# light2pwm.net
KiCad netlist of a schematic drawn in EAGLE
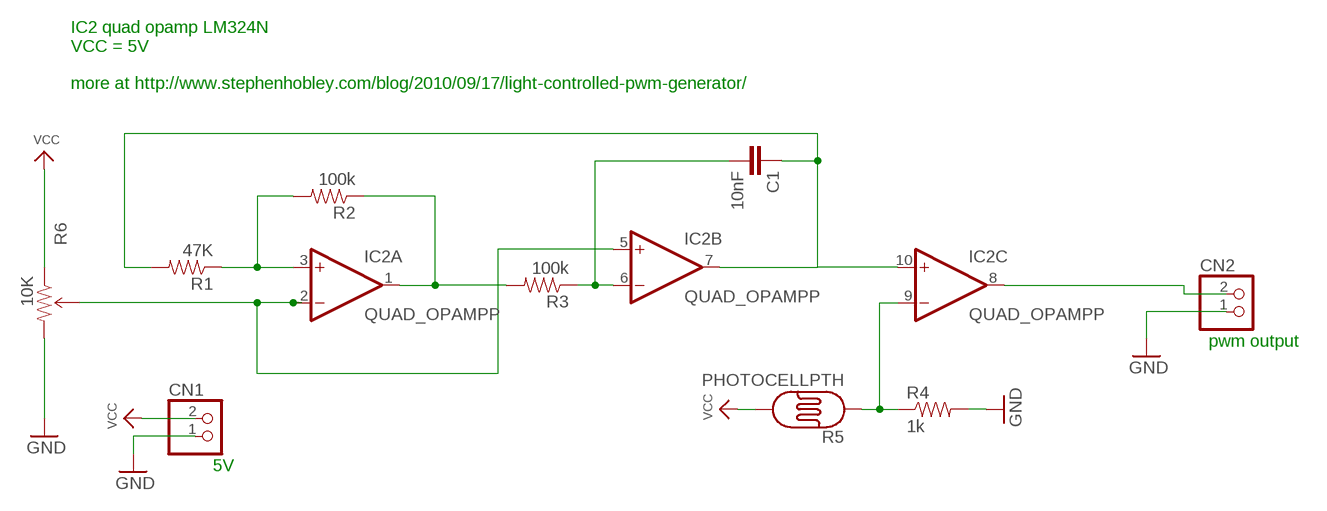
[diagram p0: schematic, sheet 1]

(export (version "E")
  (design (tool "Eeschema 10.0.6"))
  (components
    (comp (ref "C1")
      (value "10nF")
      (footprint "eagle-import:0402-CAP")
      (libsource (lib "eagle-import") (part "10NF-CER"))
    )
    (comp (ref "CN1")
      (value "JST_2PIN-THM")
      (footprint "eagle-import:JST-PH-2-THM")
      (libsource (lib "eagle-import") (part "JST_2PIN-THM"))
    )
    (comp (ref "CN2")
      (value "JST_2PIN-THM")
      (footprint "eagle-import:JST-PH-2-THM")
      (libsource (lib "eagle-import") (part "JST_2PIN-THM"))
    )
    (comp (ref "IC2")
      (value "QUAD_OPAMPP")
      (footprint "eagle-import:DIL14")
      (libsource (lib "eagle-import") (part "QUAD_OPAMPP"))
    )
    (comp (ref "R1")
      (value "47K")
      (footprint "eagle-import:AXIAL-0.3EZ")
      (libsource (lib "eagle-import") (part "RESISTOREZ"))
    )
    (comp (ref "R2")
      (value "100k")
      (footprint "eagle-import:AXIAL-0.3EZ")
      (libsource (lib "eagle-import") (part "RESISTOREZ"))
    )
    (comp (ref "R3")
      (value "100k")
      (footprint "eagle-import:AXIAL-0.3EZ")
      (libsource (lib "eagle-import") (part "RESISTOREZ"))
    )
    (comp (ref "R4")
      (value "1k")
      (footprint "eagle-import:AXIAL-0.3EZ")
      (libsource (lib "eagle-import") (part "RESISTOREZ"))
    )
    (comp (ref "R5")
      (value "PHOTOCELLPTH")
      (footprint "eagle-import:PHOTOCELL")
      (libsource (lib "eagle-import") (part "PHOTOCELLPTH"))
    )
    (comp (ref "R6")
      (value "10K")
      (footprint "eagle-import:3386U")
      (libsource (lib "eagle-import") (part "TRIMPOT-PTH-KNOB"))
    )
  )
  (nets
    (net (code "1") (name "GND") (class "Default")
      (node (ref "CN1") (pin "1") (pinfunction "2_1") (pintype "passive"))
      (node (ref "CN2") (pin "1") (pinfunction "2_1") (pintype "passive"))
      (node (ref "R4") (pin "P$2") (pinfunction "2_P$2") (pintype "passive"))
      (node (ref "R6") (pin "3") (pinfunction "CW_3") (pintype "passive"))
    )
    (net (code "2") (name "Net-(CN2-1)") (class "Default")
      (node (ref "CN2") (pin "2") (pinfunction "1_2") (pintype "passive"))
      (node (ref "IC2") (pin "8") (pinfunction "OUT_8") (pintype "output"))
    )
    (net (code "3") (name "Net-(IC2A-+IN)") (class "Default")
      (node (ref "IC2") (pin "3") (pinfunction "+IN_3") (pintype "input"))
      (node (ref "R1") (pin "P$1") (pinfunction "1_P$1") (pintype "passive"))
      (node (ref "R2") (pin "P$2") (pinfunction "2_P$2") (pintype "passive"))
    )
    (net (code "4") (name "Net-(IC2A--IN)") (class "Default")
      (node (ref "IC2") (pin "2") (pinfunction "-IN_2") (pintype "input"))
      (node (ref "IC2") (pin "5") (pinfunction "+IN_5") (pintype "input"))
      (node (ref "R6") (pin "2") (pinfunction "WIPER_2") (pintype "passive"))
    )
    (net (code "5") (name "Net-(IC2A-OUT)") (class "Default")
      (node (ref "IC2") (pin "1") (pinfunction "OUT_1") (pintype "output"))
      (node (ref "R2") (pin "P$1") (pinfunction "1_P$1") (pintype "passive"))
      (node (ref "R3") (pin "P$2") (pinfunction "2_P$2") (pintype "passive"))
    )
    (net (code "6") (name "Net-(IC2B--IN)") (class "Default")
      (node (ref "C1") (pin "2") (pinfunction "2_2") (pintype "passive"))
      (node (ref "IC2") (pin "6") (pinfunction "-IN_6") (pintype "input"))
      (node (ref "R3") (pin "P$1") (pinfunction "1_P$1") (pintype "passive"))
    )
    (net (code "7") (name "Net-(IC2B-OUT)") (class "Default")
      (node (ref "C1") (pin "1") (pinfunction "1_1") (pintype "passive"))
      (node (ref "IC2") (pin "10") (pinfunction "+IN_10") (pintype "input"))
      (node (ref "IC2") (pin "7") (pinfunction "OUT_7") (pintype "output"))
      (node (ref "R1") (pin "P$2") (pinfunction "2_P$2") (pintype "passive"))
    )
    (net (code "8") (name "Net-(IC2C--IN)") (class "Default")
      (node (ref "IC2") (pin "9") (pinfunction "-IN_9") (pintype "input"))
      (node (ref "R4") (pin "P$1") (pinfunction "1_P$1") (pintype "passive"))
      (node (ref "R5") (pin "1") (pinfunction "P$1_1") (pintype "bidirectional"))
    )
    (net (code "9") (name "VCC") (class "Default")
      (node (ref "CN1") (pin "2") (pinfunction "1_2") (pintype "passive"))
      (node (ref "R5") (pin "2") (pinfunction "P$2_2") (pintype "bidirectional"))
      (node (ref "R6") (pin "1") (pinfunction "CCW_1") (pintype "passive"))
    )
  )
)
